# aNoInv.net
KiCad netlist of a schematic drawn in Altium Designer
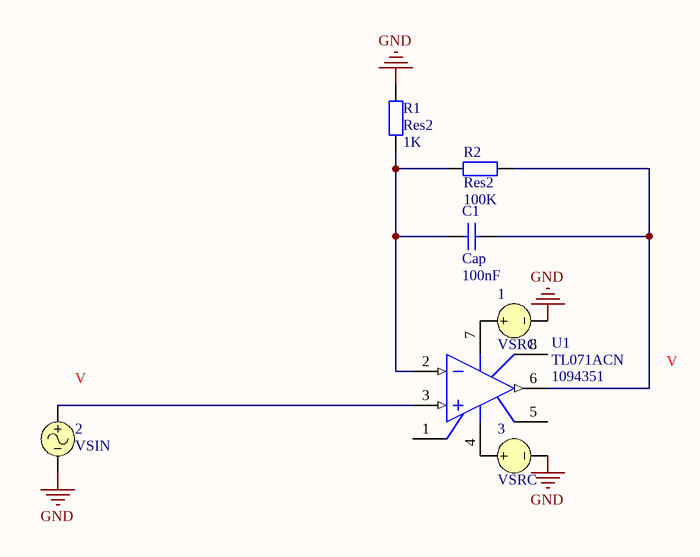
[diagram p0: aNoInv.SchDoc]

(export (version "E")
  (design (tool "Eeschema 10.0.6"))
  (components
    (comp (ref "1")
      (value "VSRC")
      (description "Voltage Source")
      (fields (field (name "PUBLISHER") "Altium Limited"))
      (libsource (lib "Simulation Sources") (part "VSRC"))
    )
    (comp (ref "2")
      (value "VSIN")
      (description "Sinusoidal Voltage Source")
      (fields (field (name "PUBLISHER") "Altium Limited"))
      (libsource (lib "Simulation Sources") (part "VSIN"))
    )
    (comp (ref "3")
      (value "VSRC")
      (description "Voltage Source")
      (fields (field (name "PUBLISHER") "Altium Limited"))
      (libsource (lib "Simulation Sources") (part "VSRC"))
    )
    (comp (ref "C1")
      (value "Cap")
      (footprint "RAD-0.3")
      (description "Capacitor")
      (fields (field (name "ALTIUM_VALUE") "100nF") (field (name "PUBLISHER") "Altium Limited"))
      (libsource (lib "Miscellaneous Devices") (part "Cap"))
    )
    (comp (ref "R1")
      (value "Res2")
      (footprint "AXIAL-0.4")
      (description "Resistor")
      (fields (field (name "ALTIUM_VALUE") "1K") (field (name "PUBLISHER") "Altium Limited"))
      (libsource (lib "Miscellaneous Devices") (part "Res2"))
    )
    (comp (ref "R2")
      (value "Res2")
      (footprint "AXIAL-0.4")
      (description "Resistor")
      (fields (field (name "ALTIUM_VALUE") "100K") (field (name "PUBLISHER") "Altium Limited"))
      (libsource (lib "") (part "Res2_1"))
    )
    (comp (ref "U1")
      (value "TL071ACN")
      (footprint "DIP8")
      (description "Low-Noise J-FET Single Operational Amplifier")
      (fields
        (field (name "SUPPLIER PART NUMBER 1") "1094351")
        (field (name "MANUFACTURER") "STMicroelectronics")
        (field (name "MANUFACTURER PART NUMBER") "TL071CN")
        (field (name "PUBLISHER") "Altium Limited")
      )
      (libsource (lib "ST Operational Amplifier") (part "TL071ACN"))
    )
  )
  (nets
    (net (code "1") (name "GND") (class "Default")
      (node (ref "1") (pin "2") (pinfunction "2_2") (pintype "passive"))
      (node (ref "2") (pin "2") (pinfunction "2_2") (pintype "passive"))
      (node (ref "3") (pin "2") (pinfunction "2_2") (pintype "passive"))
      (node (ref "R1") (pin "2") (pinfunction "2_2") (pintype "passive"))
    )
    (net (code "2") (name "Net-(U1-IN+)") (class "Default")
      (node (ref "2") (pin "1") (pinfunction "1_1") (pintype "passive"))
      (node (ref "U1") (pin "3") (pinfunction "IN+_3") (pintype "input"))
    )
    (net (code "3") (name "Net-(U1-IN-)") (class "Default")
      (node (ref "C1") (pin "1") (pinfunction "1_1") (pintype "passive"))
      (node (ref "R1") (pin "1") (pinfunction "1_1") (pintype "passive"))
      (node (ref "R2") (pin "1") (pinfunction "1_1") (pintype "passive"))
      (node (ref "U1") (pin "2") (pinfunction "IN-_2") (pintype "input"))
    )
    (net (code "4") (name "Net-(U1-OUT)") (class "Default")
      (node (ref "C1") (pin "2") (pinfunction "2_2") (pintype "passive"))
      (node (ref "R2") (pin "2") (pinfunction "2_2") (pintype "passive"))
      (node (ref "U1") (pin "6") (pinfunction "OUT_6") (pintype "output"))
    )
    (net (code "5") (name "Net-(U1-V+)") (class "Default")
      (node (ref "1") (pin "1") (pinfunction "1_1") (pintype "passive"))
      (node (ref "U1") (pin "7") (pinfunction "V+_7") (pintype "power_in"))
    )
    (net (code "6") (name "Net-(U1-V-)") (class "Default")
      (node (ref "3") (pin "1") (pinfunction "1_1") (pintype "passive"))
      (node (ref "U1") (pin "4") (pinfunction "V-_4") (pintype "power_in"))
    )
    (net (code "7") (name "unconnected-(U1-NC-Pad8)") (class "Default")
      (node (ref "U1") (pin "8") (pinfunction "NC_8") (pintype "passive"))
    )
    (net (code "8") (name "unconnected-(U1-OS_NULL-Pad1)") (class "Default")
      (node (ref "U1") (pin "1") (pinfunction "OS_NULL_1") (pintype "passive"))
    )
    (net (code "9") (name "unconnected-(U1-OS_NULL-Pad5)") (class "Default")
      (node (ref "U1") (pin "5") (pinfunction "OS_NULL_5") (pintype "passive"))
    )
  )
)
